# schematic.net
KiCad netlist of a schematic drawn in Altium Designer
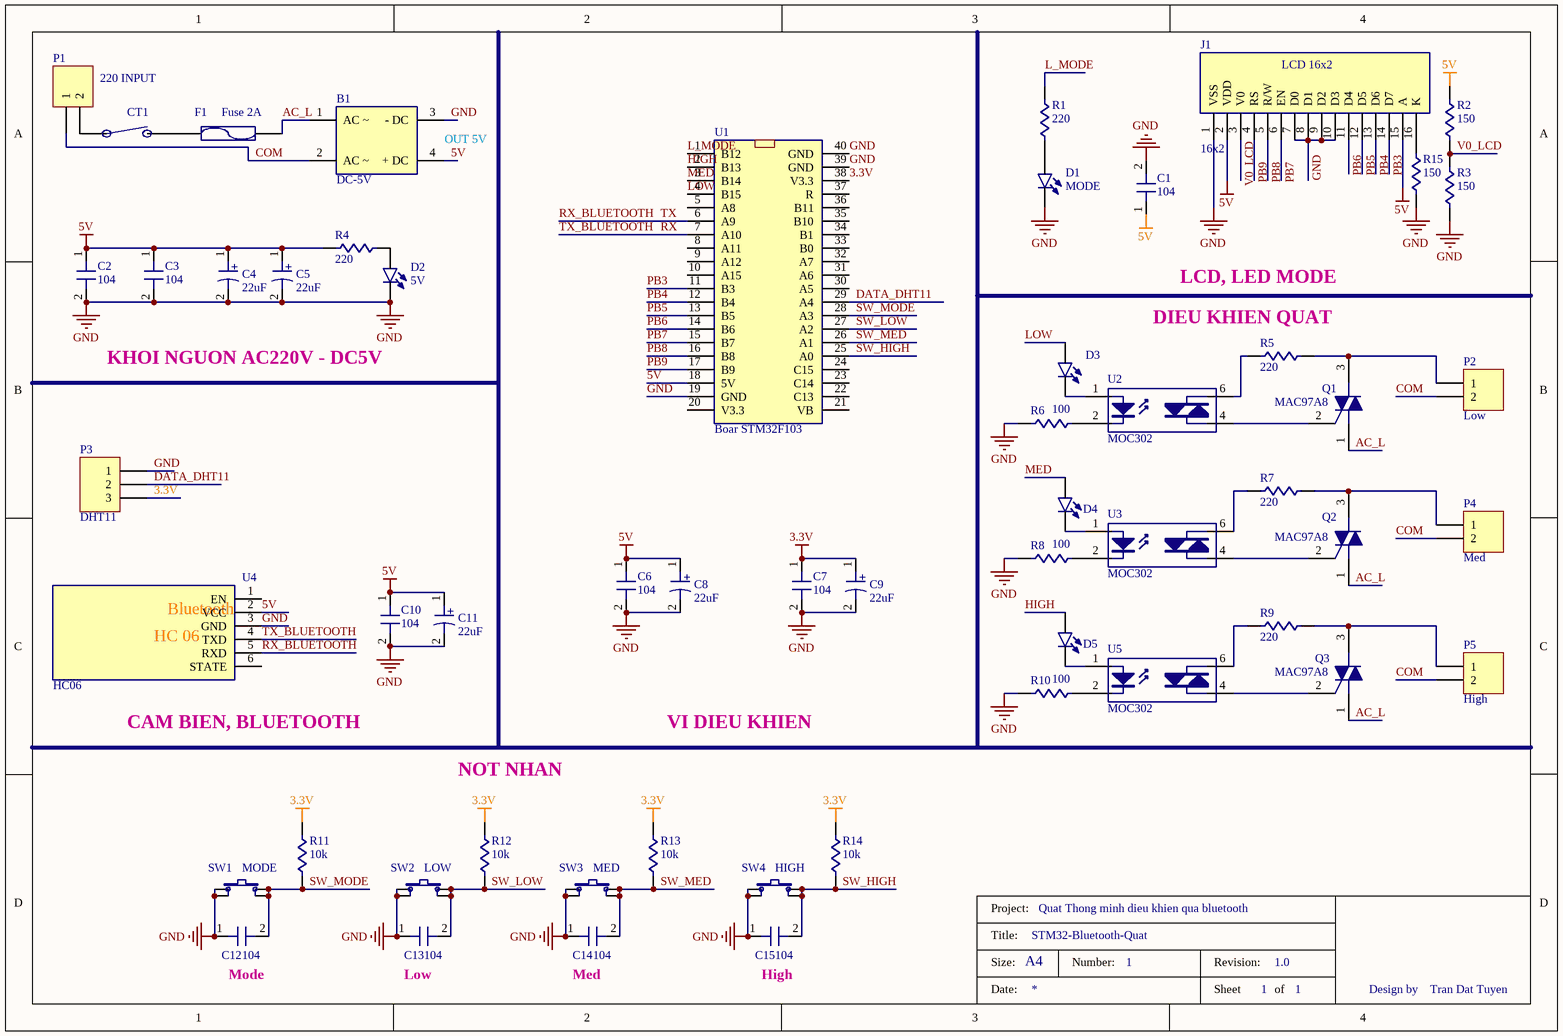
[diagram p0: schematic.SchDoc]

(export (version "E")
  (design (tool "Eeschema 10.0.6"))
  (components
    (comp (ref "B1")
      (value "DC-5V")
      (footprint "AC-DC_LK-PM01")
      (description "power 5v dc")
      (libsource (lib "tiennguyen") (part "AC-DC"))
    )
    (comp (ref "C1") (value "104") (footprint "RES0805") (libsource (lib "tiennguyen") (part "CAP")))
    (comp (ref "C2") (value "104") (footprint "RES0805") (libsource (lib "tiennguyen") (part "CAP")))
    (comp (ref "C3") (value "104") (footprint "RES0805") (libsource (lib "tiennguyen") (part "CAP")))
    (comp (ref "C4")
      (value "22uF")
      (footprint "CAP_T_3528–21_CASE-B")
      (libsource (lib "tiennguyen") (part "CAP_E"))
    )
    (comp (ref "C5")
      (value "22uF")
      (footprint "CAP_T_3528–21_CASE-B")
      (libsource (lib "tiennguyen") (part "CAP_E"))
    )
    (comp (ref "C6") (value "104") (footprint "RES0805") (libsource (lib "tiennguyen") (part "CAP")))
    (comp (ref "C7") (value "104") (footprint "RES0805") (libsource (lib "tiennguyen") (part "CAP")))
    (comp (ref "C8")
      (value "22uF")
      (footprint "CAP_T_3528–21_CASE-B")
      (libsource (lib "tiennguyen") (part "CAP_E"))
    )
    (comp (ref "C9")
      (value "22uF")
      (footprint "CAP_T_3528–21_CASE-B")
      (libsource (lib "tiennguyen") (part "CAP_E"))
    )
    (comp (ref "C10") (value "104") (footprint "RES0805") (libsource (lib "tiennguyen") (part "CAP")))
    (comp (ref "C11")
      (value "22uF")
      (footprint "CAP_T_3528–21_CASE-B")
      (libsource (lib "tiennguyen") (part "CAP_E"))
    )
    (comp (ref "C12") (value "104") (footprint "RES0805") (libsource (lib "tiennguyen") (part "CAP")))
    (comp (ref "C13") (value "104") (footprint "RES0805") (libsource (lib "tiennguyen") (part "CAP")))
    (comp (ref "C14") (value "104") (footprint "RES0805") (libsource (lib "tiennguyen") (part "CAP")))
    (comp (ref "C15") (value "104") (footprint "RES0805") (libsource (lib "tiennguyen") (part "CAP")))
    (comp (ref "CT1")
      (value "CONTAC")
      (footprint "HDR1X2200Mil")
      (libsource (lib "tiennguyen") (part "CONTAC"))
    )
    (comp (ref "D1") (value "MODE") (footprint "LED3") (libsource (lib "tiennguyen") (part "LED")))
    (comp (ref "D2") (value "5V") (footprint "LED3") (libsource (lib "tiennguyen") (part "LED")))
    (comp (ref "D3") (value "LOW") (footprint "LED3") (libsource (lib "tiennguyen") (part "LED")))
    (comp (ref "D4") (value "MED") (footprint "LED3") (libsource (lib "tiennguyen") (part "LED")))
    (comp (ref "D5") (value "SWING") (footprint "LED3") (libsource (lib "tiennguyen") (part "LED")))
    (comp (ref "F1")
      (value "Fuse 2A")
      (footprint "FUSE_PIN-W2/E2.8")
      (description "Fuse 1A 3.6mmx10mm")
      (libsource (lib "tiennguyen") (part "FUSE"))
    )
    (comp (ref "J1")
      (value "16x2")
      (footprint "LCD16x2_16PIN")
      (description "16 PIN")
      (libsource (lib "tiennguyen") (part "LCD16X2"))
    )
    (comp (ref "P1")
      (value "220 INPUT")
      (footprint "TERMINAL_2PIN_1")
      (description "Header, 2-Pin")
      (fields (field (name "PUBLISHER") "Altium Limited"))
      (libsource (lib "") (part "Header 2_1"))
    )
    (comp (ref "P2")
      (value "Low")
      (footprint "TERMINAL_2PIN_1")
      (description "Header, 2-Pin")
      (fields (field (name "PUBLISHER") "Altium Limited"))
      (libsource (lib "tiennguyen") (part "Header 2"))
    )
    (comp (ref "P3")
      (value "DHT11")
      (footprint "HDR1X3")
      (description "Header, 3-Pin")
      (fields (field (name "PUBLISHER") "Altium Limited"))
      (libsource (lib "tiennguyen") (part "Header 3"))
    )
    (comp (ref "P4")
      (value "Med")
      (footprint "TERMINAL_2PIN_1")
      (description "Header, 2-Pin")
      (fields (field (name "PUBLISHER") "Altium Limited"))
      (libsource (lib "tiennguyen") (part "Header 2"))
    )
    (comp (ref "P5")
      (value "High")
      (footprint "TERMINAL_2PIN_1")
      (description "Header, 2-Pin")
      (fields (field (name "PUBLISHER") "Altium Limited"))
      (libsource (lib "tiennguyen") (part "Header 2"))
    )
    (comp (ref "Q1")
      (value "MAC97A8")
      (footprint "TO92D")
      (description "Triac 600V 0.6A")
      (libsource (lib "tiennguyen") (part "MAC97A8"))
    )
    (comp (ref "Q2")
      (value "MAC97A8")
      (footprint "TO92D")
      (description "Triac 600V 0.6A")
      (libsource (lib "tiennguyen") (part "MAC97A8"))
    )
    (comp (ref "Q3")
      (value "MAC97A8")
      (footprint "TO92D")
      (description "Triac 600V 0.6A")
      (libsource (lib "tiennguyen") (part "MAC97A8"))
    )
    (comp (ref "R1") (value "220") (footprint "RES0805") (libsource (lib "tiennguyen") (part "RES")))
    (comp (ref "R2") (value "150") (footprint "RES0805") (libsource (lib "tiennguyen") (part "RES")))
    (comp (ref "R3") (value "150") (footprint "RES0805") (libsource (lib "tiennguyen") (part "RES")))
    (comp (ref "R4") (value "220") (footprint "RES0805") (libsource (lib "tiennguyen") (part "RES")))
    (comp (ref "R5") (value "220") (footprint "RES0805") (libsource (lib "tiennguyen") (part "RES")))
    (comp (ref "R6") (value "100") (footprint "RES0805") (libsource (lib "tiennguyen") (part "RES")))
    (comp (ref "R7") (value "220") (footprint "RES0805") (libsource (lib "tiennguyen") (part "RES")))
    (comp (ref "R8") (value "100") (footprint "RES0805") (libsource (lib "tiennguyen") (part "RES")))
    (comp (ref "R9") (value "220") (footprint "RES0805") (libsource (lib "tiennguyen") (part "RES")))
    (comp (ref "R10") (value "100") (footprint "RES0805") (libsource (lib "tiennguyen") (part "RES")))
    (comp (ref "R11") (value "10k") (footprint "RES0805") (libsource (lib "tiennguyen") (part "RES")))
    (comp (ref "R12") (value "10k") (footprint "RES0805") (libsource (lib "tiennguyen") (part "RES")))
    (comp (ref "R13") (value "10k") (footprint "RES0805") (libsource (lib "tiennguyen") (part "RES")))
    (comp (ref "R14") (value "10k") (footprint "RES0805") (libsource (lib "tiennguyen") (part "RES")))
    (comp (ref "R15") (value "150") (footprint "RES0805") (libsource (lib "tiennguyen") (part "RES")))
    (comp (ref "SW1")
      (value "MODE")
      (footprint "SW_4PIN_6x6x5")
      (libsource (lib "tiennguyen") (part "SW_4PIN"))
    )
    (comp (ref "SW2")
      (value "LOW")
      (footprint "SW_4PIN_6x6x5")
      (libsource (lib "tiennguyen") (part "SW_4PIN"))
    )
    (comp (ref "SW3")
      (value "MED")
      (footprint "SW_4PIN_6x6x5")
      (libsource (lib "tiennguyen") (part "SW_4PIN"))
    )
    (comp (ref "SW4")
      (value "HIGH")
      (footprint "SW_4PIN_6x6x5")
      (libsource (lib "tiennguyen") (part "SW_4PIN"))
    )
    (comp (ref "U1")
      (value "Boar STM32F103")
      (footprint "KIT_STM32F103C8T6_40PIN_2")
      (libsource (lib "tiennguyen") (part "STM32f103C8T6_KIT2"))
    )
    (comp (ref "U2")
      (value "MOC302")
      (footprint "DIP6")
      (description "Opto 400V")
      (libsource (lib "tiennguyen") (part "MOC3020"))
    )
    (comp (ref "U3")
      (value "MOC302")
      (footprint "DIP6")
      (description "Opto 400V")
      (libsource (lib "tiennguyen") (part "MOC3020"))
    )
    (comp (ref "U4")
      (value "HC06")
      (footprint "BLUETOOTH_HC05_MD")
      (description "bluetooth HC06")
      (libsource (lib "tiennguyen") (part "Bluetooth_HC06_MD"))
    )
    (comp (ref "U5")
      (value "MOC302")
      (footprint "DIP6")
      (description "Opto 400V")
      (libsource (lib "tiennguyen") (part "MOC3020"))
    )
  )
  (nets
    (net (code "1") (name "/AC_L") (class "Default")
      (node (ref "B1") (pin "1") (pinfunction "AC_~_1") (pintype "passive"))
      (node (ref "F1") (pin "1") (pinfunction "1_1") (pintype "passive"))
      (node (ref "Q1") (pin "1") (pinfunction "M1_1") (pintype "passive"))
      (node (ref "Q2") (pin "1") (pinfunction "M1_1") (pintype "passive"))
      (node (ref "Q3") (pin "1") (pinfunction "M1_1") (pintype "passive"))
    )
    (net (code "2") (name "/COM") (class "Default")
      (node (ref "B1") (pin "2") (pinfunction "AC_~_2") (pintype "passive"))
      (node (ref "P1") (pin "1") (pinfunction "1_1") (pintype "passive"))
      (node (ref "P2") (pin "2") (pinfunction "2_2") (pintype "passive"))
      (node (ref "P4") (pin "2") (pinfunction "2_2") (pintype "passive"))
      (node (ref "P5") (pin "2") (pinfunction "2_2") (pintype "passive"))
    )
    (net (code "3") (name "/DATA_DHT11") (class "Default")
      (node (ref "P3") (pin "2") (pinfunction "2_2") (pintype "passive"))
      (node (ref "U1") (pin "29") (pinfunction "A4_29") (pintype "passive"))
    )
    (net (code "4") (name "/HIGH") (class "Default")
      (node (ref "D5") (pin "1") (pinfunction "1_1") (pintype "passive"))
      (node (ref "U1") (pin "2") (pinfunction "B13_2") (pintype "passive"))
    )
    (net (code "5") (name "/LOW") (class "Default")
      (node (ref "D3") (pin "1") (pinfunction "1_1") (pintype "passive"))
      (node (ref "U1") (pin "4") (pinfunction "B15_4") (pintype "passive"))
    )
    (net (code "6") (name "/L_MODE") (class "Default")
      (node (ref "R1") (pin "2") (pinfunction "2_2") (pintype "passive"))
      (node (ref "U1") (pin "1") (pinfunction "B12_1") (pintype "passive"))
    )
    (net (code "7") (name "/MED") (class "Default")
      (node (ref "D4") (pin "1") (pinfunction "1_1") (pintype "passive"))
      (node (ref "U1") (pin "3") (pinfunction "B14_3") (pintype "passive"))
    )
    (net (code "8") (name "/PB3") (class "Default")
      (node (ref "J1") (pin "14") (pinfunction "D7_14") (pintype "passive"))
      (node (ref "U1") (pin "11") (pinfunction "B3_11") (pintype "passive"))
    )
    (net (code "9") (name "/PB4") (class "Default")
      (node (ref "J1") (pin "13") (pinfunction "D6_13") (pintype "passive"))
      (node (ref "U1") (pin "12") (pinfunction "B4_12") (pintype "passive"))
    )
    (net (code "10") (name "/PB5") (class "Default")
      (node (ref "J1") (pin "12") (pinfunction "D5_12") (pintype "passive"))
      (node (ref "U1") (pin "13") (pinfunction "B5_13") (pintype "passive"))
    )
    (net (code "11") (name "/PB6") (class "Default")
      (node (ref "J1") (pin "11") (pinfunction "D4_11") (pintype "passive"))
      (node (ref "U1") (pin "14") (pinfunction "B6_14") (pintype "passive"))
    )
    (net (code "12") (name "/PB7") (class "Default")
      (node (ref "J1") (pin "6") (pinfunction "EN_6") (pintype "passive"))
      (node (ref "U1") (pin "15") (pinfunction "B7_15") (pintype "passive"))
    )
    (net (code "13") (name "/PB8") (class "Default")
      (node (ref "J1") (pin "5") (pinfunction "R/W_5") (pintype "passive"))
      (node (ref "U1") (pin "16") (pinfunction "B8_16") (pintype "passive"))
    )
    (net (code "14") (name "/PB9") (class "Default")
      (node (ref "J1") (pin "4") (pinfunction "RS_4") (pintype "passive"))
      (node (ref "U1") (pin "17") (pinfunction "B9_17") (pintype "passive"))
    )
    (net (code "15") (name "/RX") (class "Default")
      (node (ref "U1") (pin "7") (pinfunction "A10_7") (pintype "passive"))
      (node (ref "U4") (pin "4") (pinfunction "TXD_4") (pintype "passive"))
    )
    (net (code "16") (name "/RX_BLUETOOTH") (class "Default")
      (node (ref "U1") (pin "6") (pinfunction "A9_6") (pintype "passive"))
      (node (ref "U4") (pin "5") (pinfunction "RXD_5") (pintype "passive"))
    )
    (net (code "17") (name "/SW_HIGH") (class "Default")
      (node (ref "C15") (pin "2") (pinfunction "2_2") (pintype "passive"))
      (node (ref "R14") (pin "1") (pinfunction "1_1") (pintype "passive"))
      (node (ref "SW4") (pin "3") (pinfunction "3_3") (pintype "passive"))
      (node (ref "SW4") (pin "4") (pinfunction "4_4") (pintype "passive"))
      (node (ref "U1") (pin "25") (pinfunction "A0_25") (pintype "passive"))
    )
    (net (code "18") (name "/SW_LOW") (class "Default")
      (node (ref "C13") (pin "2") (pinfunction "2_2") (pintype "passive"))
      (node (ref "R12") (pin "1") (pinfunction "1_1") (pintype "passive"))
      (node (ref "SW2") (pin "3") (pinfunction "3_3") (pintype "passive"))
      (node (ref "SW2") (pin "4") (pinfunction "4_4") (pintype "passive"))
      (node (ref "U1") (pin "27") (pinfunction "A2_27") (pintype "passive"))
    )
    (net (code "19") (name "/SW_MED") (class "Default")
      (node (ref "C14") (pin "2") (pinfunction "2_2") (pintype "passive"))
      (node (ref "R13") (pin "1") (pinfunction "1_1") (pintype "passive"))
      (node (ref "SW3") (pin "3") (pinfunction "3_3") (pintype "passive"))
      (node (ref "SW3") (pin "4") (pinfunction "4_4") (pintype "passive"))
      (node (ref "U1") (pin "26") (pinfunction "A1_26") (pintype "passive"))
    )
    (net (code "20") (name "/SW_MODE") (class "Default")
      (node (ref "C12") (pin "2") (pinfunction "2_2") (pintype "passive"))
      (node (ref "R11") (pin "1") (pinfunction "1_1") (pintype "passive"))
      (node (ref "SW1") (pin "3") (pinfunction "3_3") (pintype "passive"))
      (node (ref "SW1") (pin "4") (pinfunction "4_4") (pintype "passive"))
      (node (ref "U1") (pin "28") (pinfunction "A3_28") (pintype "passive"))
    )
    (net (code "21") (name "/V0_LCD") (class "Default")
      (node (ref "J1") (pin "3") (pinfunction "V0_3") (pintype "passive"))
      (node (ref "R2") (pin "1") (pinfunction "1_1") (pintype "passive"))
      (node (ref "R3") (pin "2") (pinfunction "2_2") (pintype "passive"))
    )
    (net (code "22") (name "3.3V") (class "Default")
      (node (ref "C7") (pin "1") (pinfunction "1_1") (pintype "passive"))
      (node (ref "C9") (pin "1") (pinfunction "1_1") (pintype "passive"))
      (node (ref "P3") (pin "3") (pinfunction "3_3") (pintype "passive"))
      (node (ref "R11") (pin "2") (pinfunction "2_2") (pintype "passive"))
      (node (ref "R12") (pin "2") (pinfunction "2_2") (pintype "passive"))
      (node (ref "R13") (pin "2") (pinfunction "2_2") (pintype "passive"))
      (node (ref "R14") (pin "2") (pinfunction "2_2") (pintype "passive"))
      (node (ref "U1") (pin "38") (pinfunction "V3.3_38") (pintype "passive"))
    )
    (net (code "23") (name "5V") (class "Default")
      (node (ref "B1") (pin "4") (pinfunction "+_DC_4") (pintype "passive"))
      (node (ref "C1") (pin "1") (pinfunction "1_1") (pintype "passive"))
      (node (ref "C10") (pin "1") (pinfunction "1_1") (pintype "passive"))
      (node (ref "C11") (pin "1") (pinfunction "1_1") (pintype "passive"))
      (node (ref "C2") (pin "1") (pinfunction "1_1") (pintype "passive"))
      (node (ref "C3") (pin "1") (pinfunction "1_1") (pintype "passive"))
      (node (ref "C4") (pin "1") (pinfunction "1_1") (pintype "passive"))
      (node (ref "C5") (pin "1") (pinfunction "1_1") (pintype "passive"))
      (node (ref "C6") (pin "1") (pinfunction "1_1") (pintype "passive"))
      (node (ref "C8") (pin "1") (pinfunction "1_1") (pintype "passive"))
      (node (ref "J1") (pin "15") (pinfunction "A_15") (pintype "passive"))
      (node (ref "J1") (pin "2") (pinfunction "VDD_2") (pintype "passive"))
      (node (ref "R2") (pin "2") (pinfunction "2_2") (pintype "passive"))
      (node (ref "R4") (pin "2") (pinfunction "2_2") (pintype "passive"))
      (node (ref "U1") (pin "18") (pinfunction "5V_18") (pintype "passive"))
      (node (ref "U4") (pin "2") (pinfunction "VCC_2") (pintype "passive"))
    )
    (net (code "24") (name "GND") (class "Default")
      (node (ref "B1") (pin "3") (pinfunction "-_DC_3") (pintype "passive"))
      (node (ref "C1") (pin "2") (pinfunction "2_2") (pintype "passive"))
      (node (ref "C10") (pin "2") (pinfunction "2_2") (pintype "passive"))
      (node (ref "C11") (pin "2") (pinfunction "2_2") (pintype "passive"))
      (node (ref "C12") (pin "1") (pinfunction "1_1") (pintype "passive"))
      (node (ref "C13") (pin "1") (pinfunction "1_1") (pintype "passive"))
      (node (ref "C14") (pin "1") (pinfunction "1_1") (pintype "passive"))
      (node (ref "C15") (pin "1") (pinfunction "1_1") (pintype "passive"))
      (node (ref "C2") (pin "2") (pinfunction "2_2") (pintype "passive"))
      (node (ref "C3") (pin "2") (pinfunction "2_2") (pintype "passive"))
      (node (ref "C4") (pin "2") (pinfunction "2_2") (pintype "passive"))
      (node (ref "C5") (pin "2") (pinfunction "2_2") (pintype "passive"))
      (node (ref "C6") (pin "2") (pinfunction "2_2") (pintype "passive"))
      (node (ref "C7") (pin "2") (pinfunction "2_2") (pintype "passive"))
      (node (ref "C8") (pin "2") (pinfunction "2_2") (pintype "passive"))
      (node (ref "C9") (pin "2") (pinfunction "2_2") (pintype "passive"))
      (node (ref "D1") (pin "2") (pinfunction "2_2") (pintype "passive"))
      (node (ref "D2") (pin "2") (pinfunction "2_2") (pintype "passive"))
      (node (ref "J1") (pin "1") (pinfunction "VSS_1") (pintype "passive"))
      (node (ref "J1") (pin "10") (pinfunction "D3_10") (pintype "passive"))
      (node (ref "J1") (pin "7") (pinfunction "D0_7") (pintype "passive"))
      (node (ref "J1") (pin "8") (pinfunction "D1_8") (pintype "passive"))
      (node (ref "J1") (pin "9") (pinfunction "D2_9") (pintype "passive"))
      (node (ref "P3") (pin "1") (pinfunction "1_1") (pintype "passive"))
      (node (ref "R10") (pin "2") (pinfunction "2_2") (pintype "passive"))
      (node (ref "R15") (pin "1") (pinfunction "1_1") (pintype "passive"))
      (node (ref "R3") (pin "1") (pinfunction "1_1") (pintype "passive"))
      (node (ref "R6") (pin "2") (pinfunction "2_2") (pintype "passive"))
      (node (ref "R8") (pin "1") (pinfunction "1_1") (pintype "passive"))
      (node (ref "SW1") (pin "1") (pinfunction "1_1") (pintype "passive"))
      (node (ref "SW1") (pin "2") (pinfunction "2_2") (pintype "passive"))
      (node (ref "SW2") (pin "1") (pinfunction "1_1") (pintype "passive"))
      (node (ref "SW2") (pin "2") (pinfunction "2_2") (pintype "passive"))
      (node (ref "SW3") (pin "1") (pinfunction "1_1") (pintype "passive"))
      (node (ref "SW3") (pin "2") (pinfunction "2_2") (pintype "passive"))
      (node (ref "SW4") (pin "1") (pinfunction "1_1") (pintype "passive"))
      (node (ref "SW4") (pin "2") (pinfunction "2_2") (pintype "passive"))
      (node (ref "U1") (pin "19") (pinfunction "GND_19") (pintype "passive"))
      (node (ref "U1") (pin "39") (pinfunction "GND_39") (pintype "passive"))
      (node (ref "U1") (pin "40") (pinfunction "GND_40") (pintype "passive"))
      (node (ref "U4") (pin "3") (pinfunction "GND_3") (pintype "passive"))
    )
    (net (code "25") (name "Net-(CT1-Pad1)") (class "Default")
      (node (ref "CT1") (pin "1") (pinfunction "1_1") (pintype "passive"))
      (node (ref "P1") (pin "2") (pinfunction "2_2") (pintype "passive"))
    )
    (net (code "26") (name "Net-(CT1-Pad2)") (class "Default")
      (node (ref "CT1") (pin "2") (pinfunction "2_2") (pintype "passive"))
      (node (ref "F1") (pin "2") (pinfunction "2_2") (pintype "passive"))
    )
    (net (code "27") (name "Net-(D1-Pad1)") (class "Default")
      (node (ref "D1") (pin "1") (pinfunction "1_1") (pintype "passive"))
      (node (ref "R1") (pin "1") (pinfunction "1_1") (pintype "passive"))
    )
    (net (code "28") (name "Net-(D2-Pad1)") (class "Default")
      (node (ref "D2") (pin "1") (pinfunction "1_1") (pintype "passive"))
      (node (ref "R4") (pin "1") (pinfunction "1_1") (pintype "passive"))
    )
    (net (code "29") (name "Net-(J1-K)") (class "Default")
      (node (ref "J1") (pin "16") (pinfunction "K_16") (pintype "passive"))
      (node (ref "R15") (pin "2") (pinfunction "2_2") (pintype "passive"))
    )
    (net (code "30") (name "Net-(Q1-G)") (class "Default")
      (node (ref "Q1") (pin "2") (pinfunction "G_2") (pintype "passive"))
      (node (ref "U2") (pin "4") (pinfunction "4_4") (pintype "passive"))
    )
    (net (code "31") (name "Net-(Q1-M2)") (class "Default")
      (node (ref "P2") (pin "1") (pinfunction "1_1") (pintype "passive"))
      (node (ref "Q1") (pin "3") (pinfunction "M2_3") (pintype "passive"))
      (node (ref "R5") (pin "1") (pinfunction "1_1") (pintype "passive"))
    )
    (net (code "32") (name "Net-(Q2-G)") (class "Default")
      (node (ref "Q2") (pin "2") (pinfunction "G_2") (pintype "passive"))
      (node (ref "U3") (pin "4") (pinfunction "4_4") (pintype "passive"))
    )
    (net (code "33") (name "Net-(Q2-M2)") (class "Default")
      (node (ref "P4") (pin "1") (pinfunction "1_1") (pintype "passive"))
      (node (ref "Q2") (pin "3") (pinfunction "M2_3") (pintype "passive"))
      (node (ref "R7") (pin "1") (pinfunction "1_1") (pintype "passive"))
    )
    (net (code "34") (name "Net-(Q3-G)") (class "Default")
      (node (ref "Q3") (pin "2") (pinfunction "G_2") (pintype "passive"))
      (node (ref "U5") (pin "4") (pinfunction "4_4") (pintype "passive"))
    )
    (net (code "35") (name "Net-(Q3-M2)") (class "Default")
      (node (ref "P5") (pin "1") (pinfunction "1_1") (pintype "passive"))
      (node (ref "Q3") (pin "3") (pinfunction "M2_3") (pintype "passive"))
      (node (ref "R9") (pin "1") (pinfunction "1_1") (pintype "passive"))
    )
    (net (code "36") (name "Net-(R5-Pad2)") (class "Default")
      (node (ref "R5") (pin "2") (pinfunction "2_2") (pintype "passive"))
      (node (ref "U2") (pin "6") (pinfunction "6_6") (pintype "passive"))
    )
    (net (code "37") (name "Net-(R7-Pad2)") (class "Default")
      (node (ref "R7") (pin "2") (pinfunction "2_2") (pintype "passive"))
      (node (ref "U3") (pin "6") (pinfunction "6_6") (pintype "passive"))
    )
    (net (code "38") (name "Net-(R9-Pad2)") (class "Default")
      (node (ref "R9") (pin "2") (pinfunction "2_2") (pintype "passive"))
      (node (ref "U5") (pin "6") (pinfunction "6_6") (pintype "passive"))
    )
    (net (code "39") (name "Net-(U2-A)") (class "Default")
      (node (ref "D3") (pin "2") (pinfunction "2_2") (pintype "passive"))
      (node (ref "U2") (pin "1") (pinfunction "A_1") (pintype "passive"))
    )
    (net (code "40") (name "Net-(U2-K)") (class "Default")
      (node (ref "R6") (pin "1") (pinfunction "1_1") (pintype "passive"))
      (node (ref "U2") (pin "2") (pinfunction "K_2") (pintype "passive"))
    )
    (net (code "41") (name "Net-(U3-A)") (class "Default")
      (node (ref "D4") (pin "2") (pinfunction "2_2") (pintype "passive"))
      (node (ref "U3") (pin "1") (pinfunction "A_1") (pintype "passive"))
    )
    (net (code "42") (name "Net-(U3-K)") (class "Default")
      (node (ref "R8") (pin "2") (pinfunction "2_2") (pintype "passive"))
      (node (ref "U3") (pin "2") (pinfunction "K_2") (pintype "passive"))
    )
    (net (code "43") (name "Net-(U5-A)") (class "Default")
      (node (ref "D5") (pin "2") (pinfunction "2_2") (pintype "passive"))
      (node (ref "U5") (pin "1") (pinfunction "A_1") (pintype "passive"))
    )
    (net (code "44") (name "Net-(U5-K)") (class "Default")
      (node (ref "R10") (pin "1") (pinfunction "1_1") (pintype "passive"))
      (node (ref "U5") (pin "2") (pinfunction "K_2") (pintype "passive"))
    )
    (net (code "45") (name "unconnected-(U1-A5-Pad30)") (class "Default")
      (node (ref "U1") (pin "30") (pinfunction "A5_30") (pintype "passive"))
    )
    (net (code "46") (name "unconnected-(U1-A6-Pad31)") (class "Default")
      (node (ref "U1") (pin "31") (pinfunction "A6_31") (pintype "passive"))
    )
    (net (code "47") (name "unconnected-(U1-A7-Pad32)") (class "Default")
      (node (ref "U1") (pin "32") (pinfunction "A7_32") (pintype "passive"))
    )
    (net (code "48") (name "unconnected-(U1-A8-Pad5)") (class "Default")
      (node (ref "U1") (pin "5") (pinfunction "A8_5") (pintype "passive"))
    )
    (net (code "49") (name "unconnected-(U1-A11-Pad8)") (class "Default")
      (node (ref "U1") (pin "8") (pinfunction "A11_8") (pintype "passive"))
    )
    (net (code "50") (name "unconnected-(U1-A12-Pad9)") (class "Default")
      (node (ref "U1") (pin "9") (pinfunction "A12_9") (pintype "passive"))
    )
    (net (code "51") (name "unconnected-(U1-A15-Pad10)") (class "Default")
      (node (ref "U1") (pin "10") (pinfunction "A15_10") (pintype "passive"))
    )
    (net (code "52") (name "unconnected-(U1-B0-Pad33)") (class "Default")
      (node (ref "U1") (pin "33") (pinfunction "B0_33") (pintype "passive"))
    )
    (net (code "53") (name "unconnected-(U1-B1-Pad34)") (class "Default")
      (node (ref "U1") (pin "34") (pinfunction "B1_34") (pintype "passive"))
    )
    (net (code "54") (name "unconnected-(U1-B10-Pad35)") (class "Default")
      (node (ref "U1") (pin "35") (pinfunction "B10_35") (pintype "passive"))
    )
    (net (code "55") (name "unconnected-(U1-B11-Pad36)") (class "Default")
      (node (ref "U1") (pin "36") (pinfunction "B11_36") (pintype "passive"))
    )
    (net (code "56") (name "unconnected-(U1-C13-Pad22)") (class "Default")
      (node (ref "U1") (pin "22") (pinfunction "C13_22") (pintype "passive"))
    )
    (net (code "57") (name "unconnected-(U1-C14-Pad23)") (class "Default")
      (node (ref "U1") (pin "23") (pinfunction "C14_23") (pintype "passive"))
    )
    (net (code "58") (name "unconnected-(U1-C15-Pad24)") (class "Default")
      (node (ref "U1") (pin "24") (pinfunction "C15_24") (pintype "passive"))
    )
    (net (code "59") (name "unconnected-(U1-R-Pad37)") (class "Default")
      (node (ref "U1") (pin "37") (pinfunction "R_37") (pintype "passive"))
    )
    (net (code "60") (name "unconnected-(U1-V3.3-Pad20)") (class "Default")
      (node (ref "U1") (pin "20") (pinfunction "V3.3_20") (pintype "passive"))
    )
    (net (code "61") (name "unconnected-(U1-VB-Pad21)") (class "Default")
      (node (ref "U1") (pin "21") (pinfunction "VB_21") (pintype "passive"))
    )
    (net (code "62") (name "unconnected-(U2-NC-Pad3)") (class "Default")
      (node (ref "U2") (pin "3") (pinfunction "NC_3") (pintype "passive"))
    )
    (net (code "63") (name "unconnected-(U2-NC-Pad5)") (class "Default")
      (node (ref "U2") (pin "5") (pinfunction "NC_5") (pintype "passive"))
    )
    (net (code "64") (name "unconnected-(U3-NC-Pad3)") (class "Default")
      (node (ref "U3") (pin "3") (pinfunction "NC_3") (pintype "passive"))
    )
    (net (code "65") (name "unconnected-(U3-NC-Pad5)") (class "Default")
      (node (ref "U3") (pin "5") (pinfunction "NC_5") (pintype "passive"))
    )
    (net (code "66") (name "unconnected-(U4-EN-Pad1)") (class "Default")
      (node (ref "U4") (pin "1") (pinfunction "EN_1") (pintype "passive"))
    )
    (net (code "67") (name "unconnected-(U4-STATE-Pad6)") (class "Default")
      (node (ref "U4") (pin "6") (pinfunction "STATE_6") (pintype "passive"))
    )
    (net (code "68") (name "unconnected-(U5-NC-Pad3)") (class "Default")
      (node (ref "U5") (pin "3") (pinfunction "NC_3") (pintype "passive"))
    )
    (net (code "69") (name "unconnected-(U5-NC-Pad5)") (class "Default")
      (node (ref "U5") (pin "5") (pinfunction "NC_5") (pintype "passive"))
    )
  )
)
